# LPCB235_-_RM48_-_MAIN.net
KiCad netlist of a schematic drawn in Altium Designer
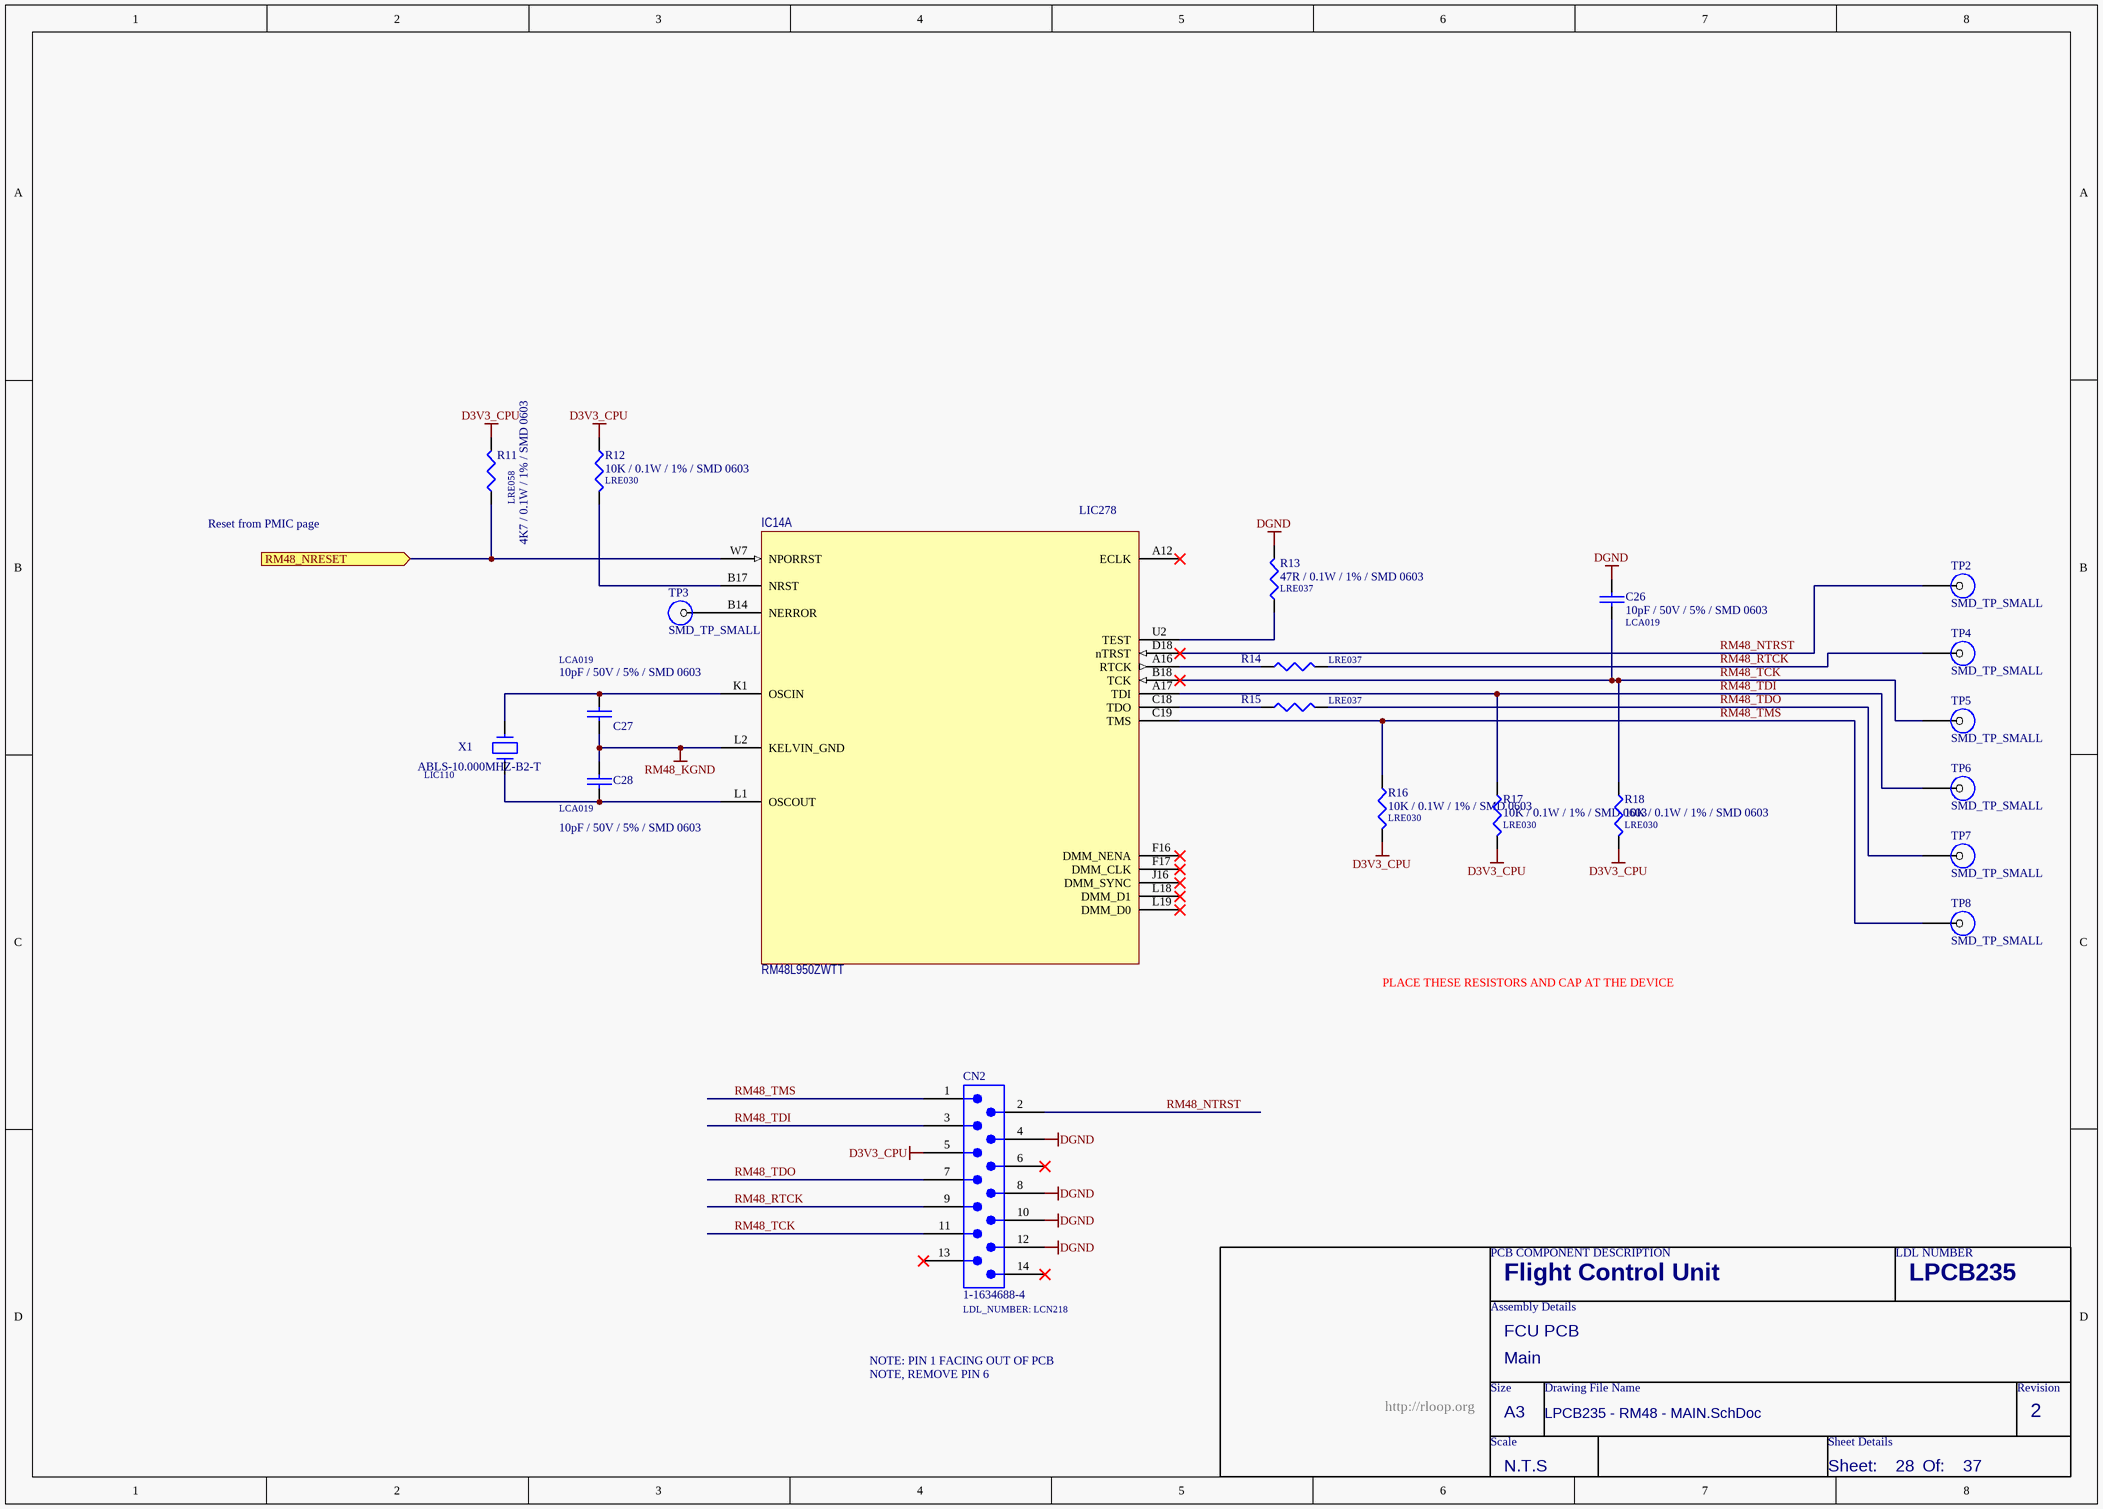
[diagram p0: LPCB235 - RM48 - MAIN.SchDoc]

(export (version "E")
  (design (tool "Eeschema 10.0.6"))
  (components
    (comp (ref "C26")
      (value "10pF / 50V / 5% / SMD 0603")
      (footprint "LFP011__CC1608-0603-IPC7351_B")
      (description "Capacitor, Ceramic Chip, 10pF, 50V, 5%, SMD 0603 [LCA019]")
      (fields (field (name "LDL_NUMBER") "LCA019"))
      (libsource (lib "LDL_Capacitors") (part "10pF / 50V / 5% / SMD 0603"))
    )
    (comp (ref "C27")
      (value "10pF / 50V / 5% / SMD 0603")
      (footprint "LFP011__CC1608-0603-IPC7351_B")
      (description "Capacitor, Ceramic Chip, 10pF, 50V, 5%, SMD 0603 [LCA019]")
      (fields (field (name "LDL_NUMBER") "LCA019"))
      (libsource (lib "LDL_Capacitors") (part "10pF / 50V / 5% / SMD 0603"))
    )
    (comp (ref "C28")
      (value "10pF / 50V / 5% / SMD 0603")
      (footprint "LFP011__CC1608-0603-IPC7351_B")
      (description "Capacitor, Ceramic Chip, 10pF, 50V, 5%, SMD 0603 [LCA019]")
      (fields (field (name "LDL_NUMBER") "LCA019"))
      (libsource (lib "LDL_Capacitors") (part "10pF / 50V / 5% / SMD 0603"))
    )
    (comp (ref "CN2")
      (value "1-1634688-4")
      (footprint "1-1634688-4")
      (description "Connector, Box Header, 14 Way, 2.54mm Straight, PTH")
      (fields (field (name "LDL_NUMBER") "LCN218"))
      (libsource (lib "LDL_Connectors") (part "1-1634688-4"))
    )
    (comp (ref "IC14")
      (value "RM48L950ZWTT")
      (footprint "LFP054__ZWT (S-PBGA-N337)")
      (description "IC, CPU, RM48 Safety CPU, SMD NFBGA337 [LIC278]")
      (fields (field (name "LDL_NUMBER") "LIC278"))
      (libsource (lib "LDL_Semiconductors") (part "RM48L950ZWTT"))
    )
    (comp (ref "R11")
      (value "4K7 / 0.1W / 1% / SMD 0603")
      (footprint "LFP020__CR1608-0603-IPC7351_B")
      (description "Resistor, Ceramic Chip, 4K7, 0.1W, 1%, SMD 0603 [LRE058]")
      (fields (field (name "LDL_NUMBER") "LRE058"))
      (libsource (lib "LDL_Resistors") (part "4K7 / 0.1W / 1% / SMD 0603"))
    )
    (comp (ref "R12")
      (value "10K / 0.1W / 1% / SMD 0603")
      (footprint "LFP020__CR1608-0603-IPC7351_B")
      (description "Resistor, Ceramic Chip, 10K, 0.1W, 1%, SMD 0603 [LRE030]")
      (fields (field (name "LDL_NUMBER") "LRE030"))
      (libsource (lib "LDL_Resistors") (part "10K / 0.1W / 1% / SMD 0603"))
    )
    (comp (ref "R13")
      (value "47R / 0.1W / 1% / SMD 0603")
      (footprint "LFP020__CR1608-0603-IPC7351_B")
      (description "Resistor, Ceramic Chip, 47R, 0.1W, 1%, SMD 0603 [LRE037]")
      (fields (field (name "LDL_NUMBER") "LRE037"))
      (libsource (lib "LDL_Resistors") (part "47R / 0.1W / 1% / SMD 0603"))
    )
    (comp (ref "R14")
      (value "47R / 0.1W / 1% / SMD 0603")
      (footprint "LFP020__CR1608-0603-IPC7351_B")
      (description "Resistor, Ceramic Chip, 47R, 0.1W, 1%, SMD 0603 [LRE037]")
      (fields (field (name "LDL_NUMBER") "LRE037"))
      (libsource (lib "LDL_Resistors") (part "47R / 0.1W / 1% / SMD 0603"))
    )
    (comp (ref "R15")
      (value "47R / 0.1W / 1% / SMD 0603")
      (footprint "LFP020__CR1608-0603-IPC7351_B")
      (description "Resistor, Ceramic Chip, 47R, 0.1W, 1%, SMD 0603 [LRE037]")
      (fields (field (name "LDL_NUMBER") "LRE037"))
      (libsource (lib "LDL_Resistors") (part "47R / 0.1W / 1% / SMD 0603"))
    )
    (comp (ref "R16")
      (value "10K / 0.1W / 1% / SMD 0603")
      (footprint "LFP020__CR1608-0603-IPC7351_B")
      (description "Resistor, Ceramic Chip, 10K, 0.1W, 1%, SMD 0603 [LRE030]")
      (fields (field (name "LDL_NUMBER") "LRE030"))
      (libsource (lib "LDL_Resistors") (part "10K / 0.1W / 1% / SMD 0603"))
    )
    (comp (ref "R17")
      (value "10K / 0.1W / 1% / SMD 0603")
      (footprint "LFP020__CR1608-0603-IPC7351_B")
      (description "Resistor, Ceramic Chip, 10K, 0.1W, 1%, SMD 0603 [LRE030]")
      (fields (field (name "LDL_NUMBER") "LRE030"))
      (libsource (lib "LDL_Resistors") (part "10K / 0.1W / 1% / SMD 0603"))
    )
    (comp (ref "R18")
      (value "10K / 0.1W / 1% / SMD 0603")
      (footprint "LFP020__CR1608-0603-IPC7351_B")
      (description "Resistor, Ceramic Chip, 10K, 0.1W, 1%, SMD 0603 [LRE030]")
      (fields (field (name "LDL_NUMBER") "LRE030"))
      (libsource (lib "LDL_Resistors") (part "10K / 0.1W / 1% / SMD 0603"))
    )
    (comp (ref "TP2")
      (value "SMD_TP_SMALL")
      (footprint "SMD-TP-SMALL")
      (description "SMD Test Point")
      (libsource (lib "LDL_Connectors") (part "SMD_TP_SMALL"))
    )
    (comp (ref "TP3")
      (value "SMD_TP_SMALL")
      (footprint "SMD-TP-SMALL")
      (description "SMD Test Point")
      (libsource (lib "LDL_Connectors") (part "SMD_TP_SMALL"))
    )
    (comp (ref "TP4")
      (value "SMD_TP_SMALL")
      (footprint "SMD-TP-SMALL")
      (description "SMD Test Point")
      (libsource (lib "LDL_Connectors") (part "SMD_TP_SMALL"))
    )
    (comp (ref "TP5")
      (value "SMD_TP_SMALL")
      (footprint "SMD-TP-SMALL")
      (description "SMD Test Point")
      (libsource (lib "LDL_Connectors") (part "SMD_TP_SMALL"))
    )
    (comp (ref "TP6")
      (value "SMD_TP_SMALL")
      (footprint "SMD-TP-SMALL")
      (description "SMD Test Point")
      (libsource (lib "LDL_Connectors") (part "SMD_TP_SMALL"))
    )
    (comp (ref "TP7")
      (value "SMD_TP_SMALL")
      (footprint "SMD-TP-SMALL")
      (description "SMD Test Point")
      (libsource (lib "LDL_Connectors") (part "SMD_TP_SMALL"))
    )
    (comp (ref "TP8")
      (value "SMD_TP_SMALL")
      (footprint "SMD-TP-SMALL")
      (description "SMD Test Point")
      (libsource (lib "LDL_Connectors") (part "SMD_TP_SMALL"))
    )
    (comp (ref "X1")
      (value "ABLS-10.000MHZ-B2-T")
      (footprint "LFP022__XT49M")
      (description "Crystal, 10MHz, 18pF, SMD [LIC110]")
      (fields (field (name "LDL_NUMBER") "LIC110"))
      (libsource (lib "LDL_Semiconductors") (part "ABLS-10.000MHZ-B2-T"))
    )
  )
  (nets
    (net (code "1") (name "/RM48_NRESET") (class "Default")
      (node (ref "IC14") (pin "W7") (pinfunction "NPORRST_W7") (pintype "input"))
      (node (ref "R11") (pin "1") (pintype "passive"))
    )
    (net (code "2") (name "/RM48_NTRST") (class "Default")
      (node (ref "CN2") (pin "2") (pinfunction "2_2") (pintype "passive"))
      (node (ref "IC14") (pin "D18") (pinfunction "nTRST_D18") (pintype "input"))
      (node (ref "TP2") (pin "1") (pintype "passive"))
    )
    (net (code "3") (name "/RM48_RTCK") (class "Default")
      (node (ref "CN2") (pin "9") (pinfunction "9_9") (pintype "passive"))
      (node (ref "R14") (pin "2") (pintype "passive"))
      (node (ref "TP4") (pin "1") (pintype "passive"))
    )
    (net (code "4") (name "/RM48_TCK") (class "Default")
      (node (ref "C26") (pin "1") (pintype "passive"))
      (node (ref "CN2") (pin "11") (pinfunction "11_11") (pintype "passive"))
      (node (ref "IC14") (pin "B18") (pinfunction "TCK_B18") (pintype "input"))
      (node (ref "R18") (pin "1") (pintype "passive"))
      (node (ref "TP5") (pin "1") (pintype "passive"))
    )
    (net (code "5") (name "/RM48_TDI") (class "Default")
      (node (ref "CN2") (pin "3") (pinfunction "3_3") (pintype "passive"))
      (node (ref "IC14") (pin "A17") (pinfunction "TDI_A17") (pintype "passive"))
      (node (ref "R17") (pin "1") (pintype "passive"))
      (node (ref "TP6") (pin "1") (pintype "passive"))
    )
    (net (code "6") (name "/RM48_TDO") (class "Default")
      (node (ref "CN2") (pin "7") (pinfunction "7_7") (pintype "passive"))
      (node (ref "R15") (pin "2") (pintype "passive"))
      (node (ref "TP7") (pin "1") (pintype "passive"))
    )
    (net (code "7") (name "/RM48_TMS") (class "Default")
      (node (ref "CN2") (pin "1") (pinfunction "1_1") (pintype "passive"))
      (node (ref "IC14") (pin "C19") (pinfunction "TMS_C19") (pintype "passive"))
      (node (ref "R16") (pin "1") (pintype "passive"))
      (node (ref "TP8") (pin "1") (pintype "passive"))
    )
    (net (code "8") (name "D3V3_CPU") (class "Default")
      (node (ref "CN2") (pin "5") (pinfunction "5_5") (pintype "passive"))
      (node (ref "R11") (pin "2") (pintype "passive"))
      (node (ref "R12") (pin "1") (pintype "passive"))
      (node (ref "R16") (pin "2") (pintype "passive"))
      (node (ref "R17") (pin "2") (pintype "passive"))
      (node (ref "R18") (pin "2") (pintype "passive"))
    )
    (net (code "9") (name "DGND") (class "Default")
      (node (ref "C26") (pin "2") (pintype "passive"))
      (node (ref "CN2") (pin "10") (pinfunction "10_10") (pintype "passive"))
      (node (ref "CN2") (pin "12") (pinfunction "12_12") (pintype "passive"))
      (node (ref "CN2") (pin "4") (pinfunction "4_4") (pintype "passive"))
      (node (ref "CN2") (pin "8") (pinfunction "8_8") (pintype "passive"))
      (node (ref "R13") (pin "2") (pintype "passive"))
    )
    (net (code "10") (name "Net-(IC14A-NERROR)") (class "Default")
      (node (ref "IC14") (pin "B14") (pinfunction "NERROR_B14") (pintype "passive"))
      (node (ref "TP3") (pin "1") (pintype "passive"))
    )
    (net (code "11") (name "Net-(IC14A-NRST)") (class "Default")
      (node (ref "IC14") (pin "B17") (pinfunction "NRST_B17") (pintype "passive"))
      (node (ref "R12") (pin "2") (pintype "passive"))
    )
    (net (code "12") (name "Net-(IC14A-OSCIN)") (class "Default")
      (node (ref "C27") (pin "1") (pintype "passive"))
      (node (ref "IC14") (pin "K1") (pinfunction "OSCIN_K1") (pintype "passive"))
      (node (ref "X1") (pin "2") (pintype "passive"))
    )
    (net (code "13") (name "Net-(IC14A-OSCOUT)") (class "Default")
      (node (ref "C28") (pin "2") (pintype "passive"))
      (node (ref "IC14") (pin "L1") (pinfunction "OSCOUT_L1") (pintype "passive"))
      (node (ref "X1") (pin "1") (pintype "passive"))
    )
    (net (code "14") (name "Net-(IC14A-RTCK)") (class "Default")
      (node (ref "IC14") (pin "A16") (pinfunction "RTCK_A16") (pintype "output"))
      (node (ref "R14") (pin "1") (pintype "passive"))
    )
    (net (code "15") (name "Net-(IC14A-TDO)") (class "Default")
      (node (ref "IC14") (pin "C18") (pinfunction "TDO_C18") (pintype "passive"))
      (node (ref "R15") (pin "1") (pintype "passive"))
    )
    (net (code "16") (name "Net-(IC14A-TEST)") (class "Default")
      (node (ref "IC14") (pin "U2") (pinfunction "TEST_U2") (pintype "passive"))
      (node (ref "R13") (pin "1") (pintype "passive"))
    )
    (net (code "17") (name "RM48_KGND") (class "Default")
      (node (ref "C27") (pin "2") (pintype "passive"))
      (node (ref "C28") (pin "1") (pintype "passive"))
      (node (ref "IC14") (pin "L2") (pinfunction "KELVIN_GND_L2") (pintype "passive"))
    )
    (net (code "18") (name "unconnected-(CN2-Pad6)") (class "Default")
      (node (ref "CN2") (pin "6") (pinfunction "6_6") (pintype "passive+no_connect"))
    )
    (net (code "19") (name "unconnected-(CN2-Pad13)") (class "Default")
      (node (ref "CN2") (pin "13") (pinfunction "13_13") (pintype "passive+no_connect"))
    )
    (net (code "20") (name "unconnected-(CN2-Pad14)") (class "Default")
      (node (ref "CN2") (pin "14") (pinfunction "14_14") (pintype "passive+no_connect"))
    )
    (net (code "21") (name "unconnected-(IC14A-DMM_CLK-PadF17)") (class "Default")
      (node (ref "IC14") (pin "F17") (pinfunction "DMM_CLK_F17") (pintype "passive+no_connect"))
    )
    (net (code "22") (name "unconnected-(IC14A-DMM_D0-PadL19)") (class "Default")
      (node (ref "IC14") (pin "L19") (pinfunction "DMM_D0_L19") (pintype "passive+no_connect"))
    )
    (net (code "23") (name "unconnected-(IC14A-DMM_D1-PadL18)") (class "Default")
      (node (ref "IC14") (pin "L18") (pinfunction "DMM_D1_L18") (pintype "passive+no_connect"))
    )
    (net (code "24") (name "unconnected-(IC14A-DMM_NENA-PadF16)") (class "Default")
      (node (ref "IC14") (pin "F16") (pinfunction "DMM_NENA_F16") (pintype "passive+no_connect"))
    )
    (net (code "25") (name "unconnected-(IC14A-DMM_SYNC-PadJ16)") (class "Default")
      (node (ref "IC14") (pin "J16") (pinfunction "DMM_SYNC_J16") (pintype "passive+no_connect"))
    )
    (net (code "26") (name "unconnected-(IC14A-ECLK-PadA12)") (class "Default")
      (node (ref "IC14") (pin "A12") (pinfunction "ECLK_A12") (pintype "passive+no_connect"))
    )
  )
)
